# 02_-_POWER.net
KiCad netlist of a schematic drawn in Altium Designer
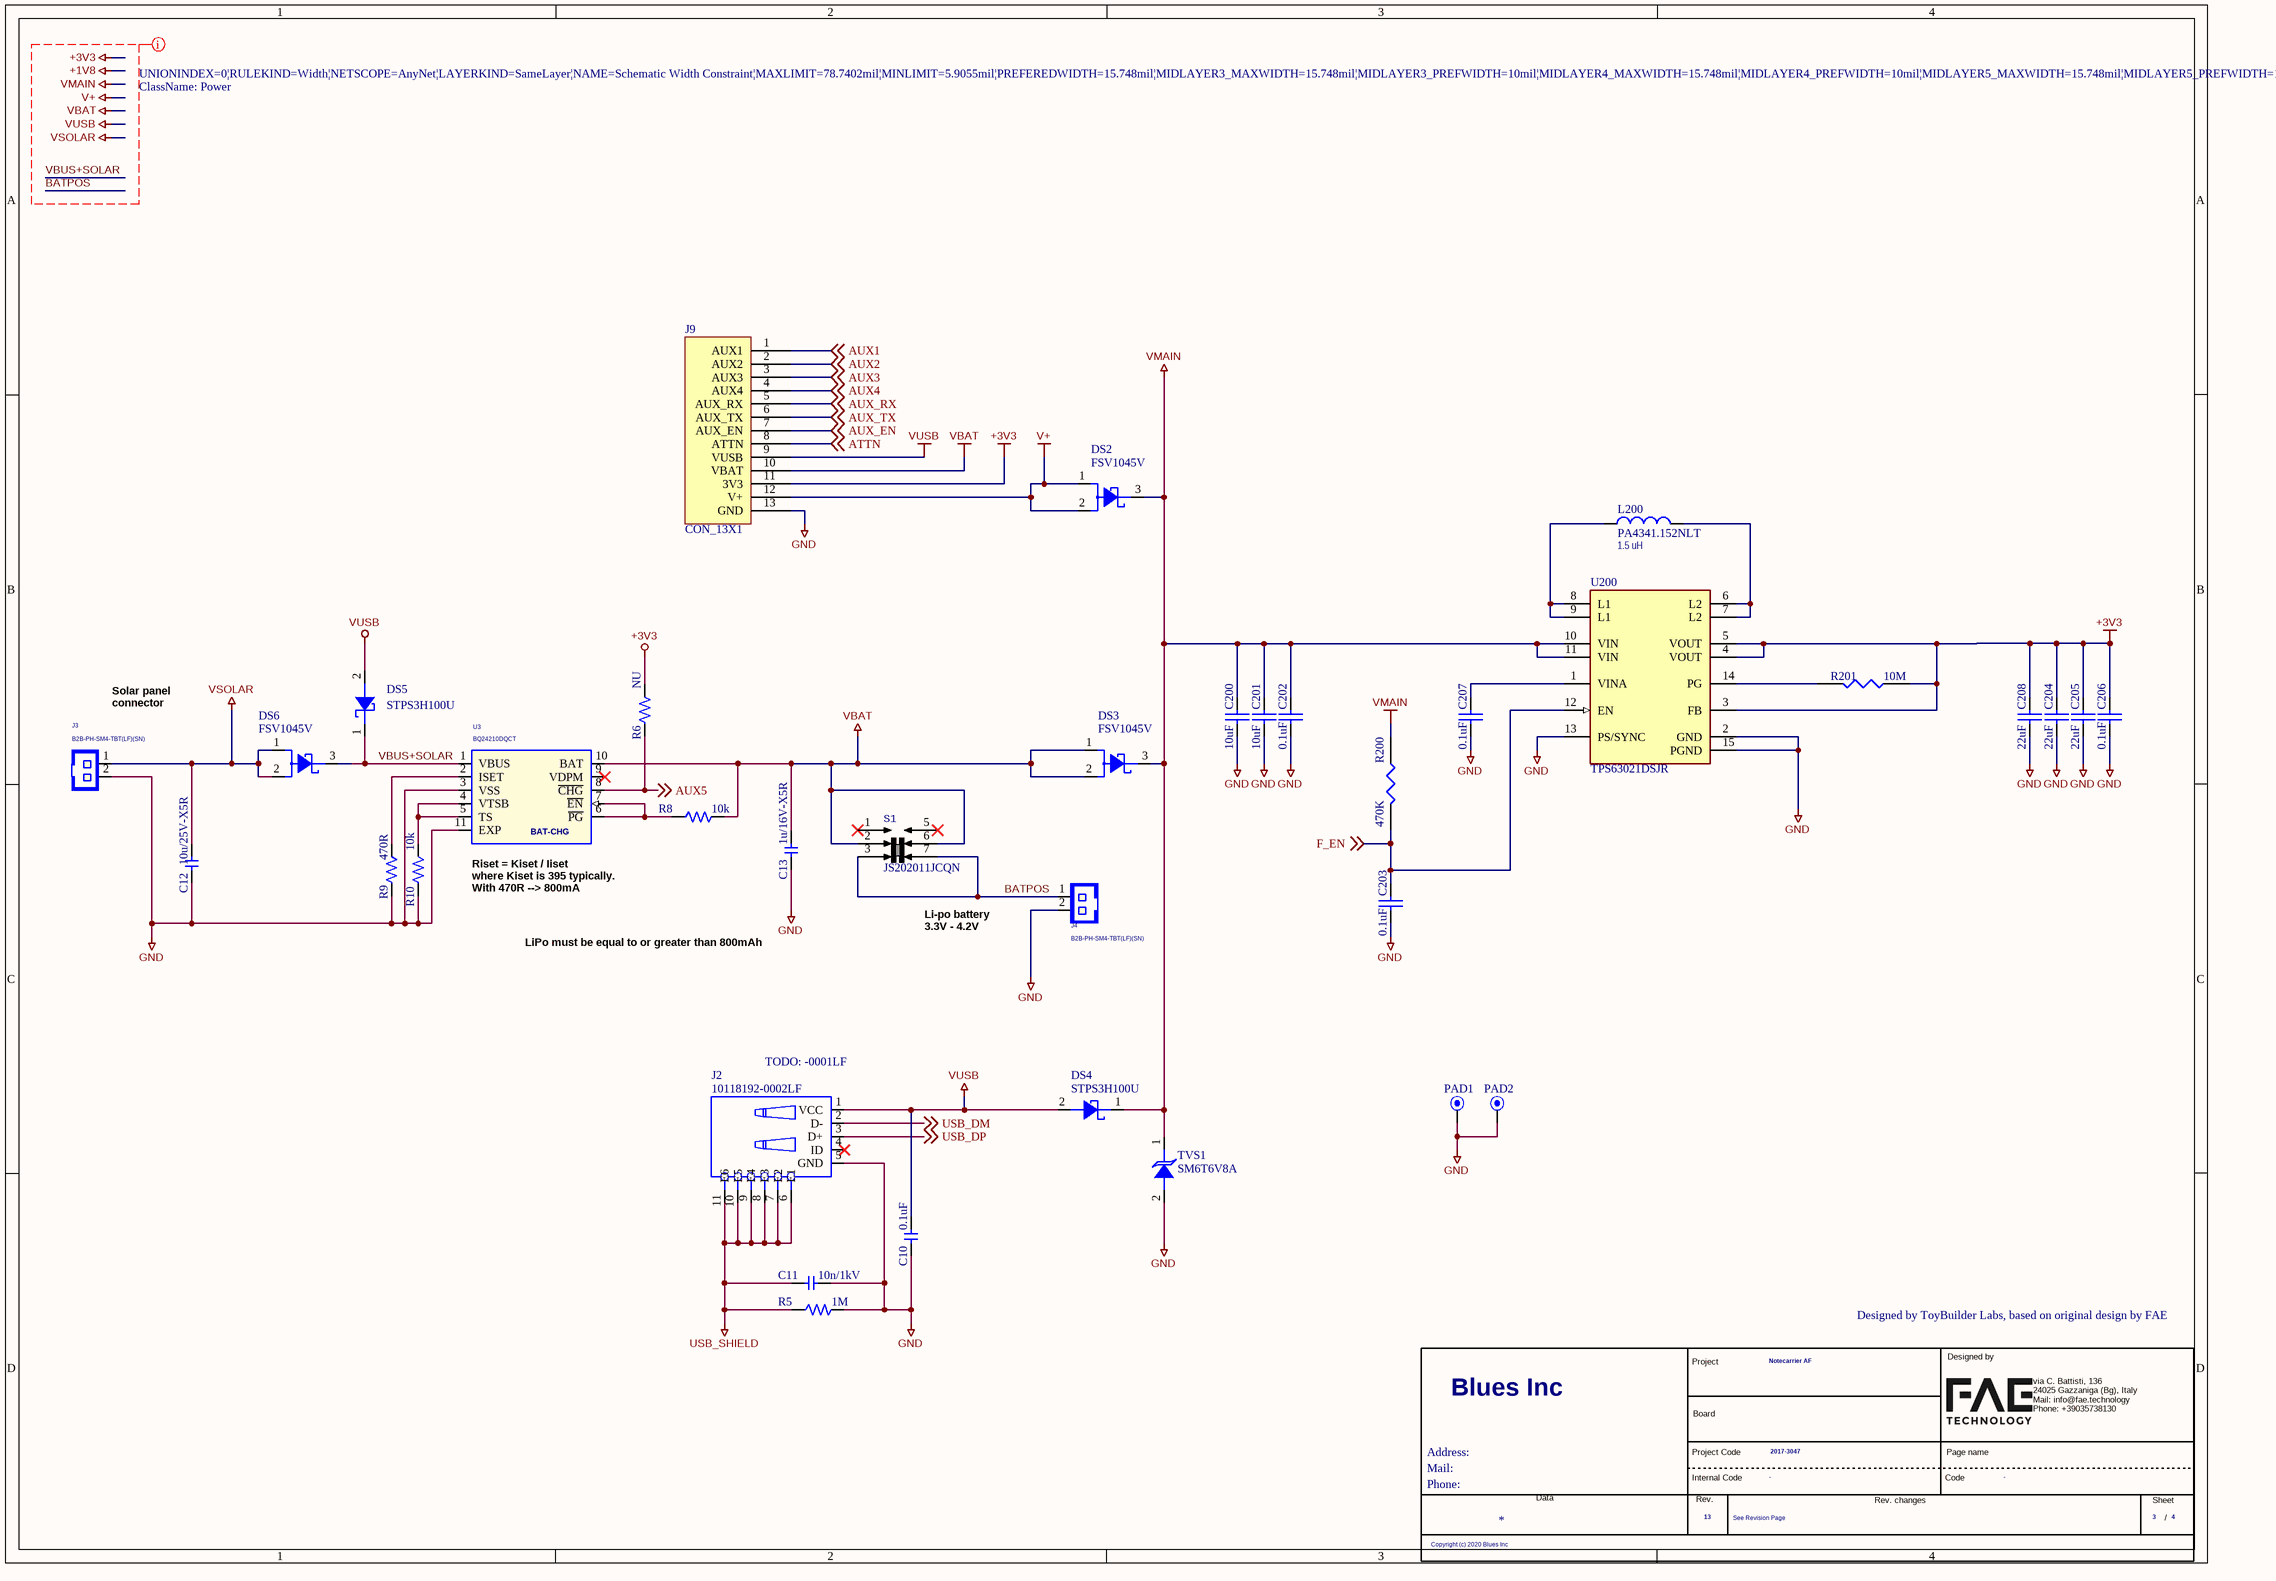
[diagram p0: 02 - POWER.SchDoc]

(export (version "E")
  (design (tool "Eeschema 10.0.6"))
  (components
    (comp (ref "*")
      (value "MyBlues")
      (fields
        (field (name "ADDRESS") "Address:")
        (field (name "COPYRIGHT") "Copyright (c) 2020 Blues Inc")
        (field (name "CUSTOMER CODE") "-")
        (field (name "CUSTOMERNAME") "Blues Inc")
        (field (name "DATABASE") "-")
        (field (name "DOCUMENTOREV") "See Revision Page")
        (field (name "MAIL") "Mail:")
        (field (name "NOME PROGETTO") "Notecarrier AF")
        (field (name "PAGE COUNT") "4")
        (field (name "PAGE NUMBER") "3")
        (field (name "PHONE") "Phone:")
        (field (name "PROJECT CODE") "2017-3047")
        (field (name "REVISION") "13")
      )
      (libsource (lib "*") (part "MyBlues"))
    )
    (comp (ref "C10")
      (value "0.1uF")
      (footprint "CS-C-0402")
      (description "CHIP CAP.CER. 100nF 16V 10% X7R 0402")
      (fields (field (name "MFR") "Yageo"))
      (libsource (lib "*") (part "CS-C-0402-100n/16V"))
    )
    (comp (ref "C11")
      (value "10n/1kV")
      (footprint "CS-C-1206")
      (description "CHIP CAP.CER. 10nF 1000V 10% X7R 1206")
      (libsource (lib "*") (part "CS-C-1206-10n/1kV"))
    )
    (comp (ref "C12")
      (value "10u/25V-X5R")
      (footprint "CS-C-1206")
      (description "CHIP CAP.CER. 10uF 25V X5R 10% 1206")
      (libsource (lib "*") (part "CS-C-1206-10u/25V-X5R"))
    )
    (comp (ref "C13")
      (value "1u/16V-X5R")
      (footprint "CS-C-0402")
      (description "CHIP CAP.CER. 1uF 16V 10% X5R 0402")
      (libsource (lib "*") (part "CS-C-0402-1u/16-X5R"))
    )
    (comp (ref "C200")
      (value "10uF")
      (footprint "0805_C")
      (description "CHIP CAP.CER. 10uF 16V 10% X7R 0805")
      (fields (field (name "MFR") "TDK"))
      (libsource (lib "Cap_SCH") (part "CAP"))
    )
    (comp (ref "C201")
      (value "10uF")
      (footprint "0805_C")
      (description "CHIP CAP.CER. 10uF 16V 10% X7R 0805")
      (fields (field (name "MFR") "TDK"))
      (libsource (lib "Cap_SCH") (part "CAP"))
    )
    (comp (ref "C202")
      (value "0.1uF")
      (footprint "CS-C-0402")
      (description "CHIP CAP.CER. 100nF 16V 10% X7R 0402")
      (fields (field (name "MFR") "Yageo"))
      (libsource (lib "Cap_SCH") (part "CAP"))
    )
    (comp (ref "C203")
      (value "0.1uF")
      (footprint "CS-C-0402")
      (description "CHIP CAP.CER. 100nF 16V 10% X7R 0402")
      (fields (field (name "MFR") "Yageo"))
      (libsource (lib "Cap_SCH") (part "CAP"))
    )
    (comp (ref "C204")
      (value "22uF")
      (footprint "0805_C")
      (description "CHIP CAP.CER. 22uF 16V 10% X7R 0805")
      (fields (field (name "MFR") "TDK"))
      (libsource (lib "Cap_SCH") (part "CAP"))
    )
    (comp (ref "C205")
      (value "22uF")
      (footprint "0805_C")
      (description "CHIP CAP.CER. 22uF 16V 10% X7R 0805")
      (fields (field (name "MFR") "TDK"))
      (libsource (lib "Cap_SCH") (part "CAP"))
    )
    (comp (ref "C206")
      (value "0.1uF")
      (footprint "CS-C-0402")
      (description "CHIP CAP.CER. 100nF 16V 10% X7R 0402")
      (fields (field (name "MFR") "Yageo"))
      (libsource (lib "Cap_SCH") (part "CAP"))
    )
    (comp (ref "C207")
      (value "0.1uF")
      (footprint "CS-C-0402")
      (description "CHIP CAP.CER. 100nF 16V 10% X7R 0402")
      (fields (field (name "MFR") "Yageo"))
      (libsource (lib "Cap_SCH") (part "CAP"))
    )
    (comp (ref "C208")
      (value "22uF")
      (footprint "0805_C")
      (description "CHIP CAP.CER. 22uF 16V 10% X7R 0805")
      (fields (field (name "MFR") "TDK"))
      (libsource (lib "Cap_SCH") (part "CAP"))
    )
    (comp (ref "DS2")
      (value "FSV1045V")
      (footprint "TO277-3")
      (description "DIODO SCHOTTKY 10A 45V FSV1045V TO277-3 SMT")
      (libsource (lib "*") (part "SCHOTTKY - FSV1045V - 10A/45V"))
    )
    (comp (ref "DS3")
      (value "FSV1045V")
      (footprint "TO277-3")
      (description "DIODO SCHOTTKY 10A 45V FSV1045V TO277-3 SMT")
      (libsource (lib "*") (part "SCHOTTKY - FSV1045V - 10A/45V"))
    )
    (comp (ref "DS4")
      (value "STPS3H100U")
      (footprint "SMB")
      (description "DIODO SCHOTTKY 3A 100V STPS3H100U SMB SMT")
      (libsource (lib "*") (part "SCHOTTKY-STPS3H100U - 3A/100V"))
    )
    (comp (ref "DS5")
      (value "STPS3H100U")
      (footprint "SMB")
      (description "DIODO SCHOTTKY 3A 100V STPS3H100U SMB SMT")
      (libsource (lib "*") (part "SCHOTTKY-STPS3H100U - 3A/100V"))
    )
    (comp (ref "DS6")
      (value "FSV1045V")
      (footprint "TO277-3")
      (description "DIODO SCHOTTKY 10A 45V FSV1045V TO277-3 SMT")
      (libsource (lib "*") (part "SCHOTTKY - FSV1045V - 10A/45V"))
    )
    (comp (ref "J2")
      (value "10118192-0002LF")
      (footprint "J-5-0065-FOS-MICROUSB10118192")
      (description "CONN. USB F/90° TIPO MICRO-B C.S. 10118192-0002LF FCI SMT")
      (libsource (lib "*") (part "USB - uUSB-B-10118192-0002LF"))
    )
    (comp (ref "J3")
      (value "B2B-PH-SM4-TBT(LF)(SN)")
      (footprint "J-2-0200-MDS-B2B-PH-SM4")
      (description "CONN. PH 2P M/D P=2 B2B-PH-SM4-TBT(LF)(SN) JST SMT")
      (libsource (lib "") (part "PH - J-2-0200-MDS-B2B-PH-SM4_1"))
    )
    (comp (ref "J4")
      (value "B2B-PH-SM4-TBT(LF)(SN)")
      (footprint "J-2-0200-MDS-B2B-PH-SM4")
      (description "CONN. PH 2P M/D P=2 B2B-PH-SM4-TBT(LF)(SN) JST SMT")
      (libsource (lib "*") (part "PH - J-2-0200-MDS-B2B-PH-SM4"))
    )
    (comp (ref "J9")
      (value "CON_13X1")
      (footprint "WE13S - 2.54")
      (libsource (lib "ATA_BLS_002_NTCR_A0-01_SCHLIB") (part "CON_13X1"))
    )
    (comp (ref "L200")
      (value "PA4341.152NLT")
      (footprint "PULSE PA4341.XXXNLT")
      (description "1.5uH, 9A SMD, (7.6 x 6.9 mm, 3.0 mm highi) 15 mOhm")
      (fields (field (name "MANUFACTURER") "Pulse") (field (name "INDUCTANCE") "1.5 uH"))
      (libsource (lib "TBL Inductors") (part "PA4341.152NLT"))
    )
    (comp (ref "PAD1")
      (value "TPS")
      (footprint "PAD-THT-CAS-0100")
      (description "Mounting Pads")
      (libsource (lib "*") (part "CASTELLATED PAD - 0100"))
    )
    (comp (ref "PAD2")
      (value "TPS")
      (footprint "PAD-THT-CAS-0100")
      (description "Mounting Pads")
      (libsource (lib "*") (part "CASTELLATED PAD - 0100"))
    )
    (comp (ref "R5")
      (value "1M")
      (footprint "RS-1206")
      (description "CHIP RES. 1M 1206 1/4W 1%")
      (libsource (lib "*") (part "RS-1206-1M"))
    )
    (comp (ref "R6")
      (value "NU")
      (footprint "RS-0402")
      (description "CHIP RES. 10K 0402 1/16W 1%")
      (libsource (lib "*") (part "RS-0402-10k"))
    )
    (comp (ref "R8")
      (value "10k")
      (footprint "RS-0402")
      (description "CHIP RES. 10K 0402 1/16W 1%")
      (libsource (lib "*") (part "RS-0402-10k"))
    )
    (comp (ref "R9")
      (value "470R")
      (footprint "RS-0402")
      (description "CHIP RES. 470R 0402 1/16W 1%")
      (libsource (lib "*") (part "RS-0402-470r"))
    )
    (comp (ref "R10")
      (value "10k")
      (footprint "RS-0402")
      (description "CHIP RES. 10K 0402 1/16W 1%")
      (libsource (lib "*") (part "RS-0402-10k"))
    )
    (comp (ref "R200")
      (value "470K")
      (footprint "RS-0402")
      (description "CHIP RES. 470K 0402 1/16W 1%")
      (fields (field (name "MFR") "Vishay / Dale"))
      (libsource (lib "Res_SCH") (part "R1_S"))
    )
    (comp (ref "R201")
      (value "10M")
      (footprint "RS-0402")
      (description "CHIP RES. 10M 0402 1/16W 1%")
      (fields (field (name "MFR") "Vishay / Dale"))
      (libsource (lib "Res_SCH") (part "R1_S"))
    )
    (comp (ref "S1")
      (value "JS202011JCQN")
      (footprint "CK_JS202011JCQN")
      (description "SWITCH SLIDE DPDT 300MA 6V, SMD, J-lead")
      (fields (field (name "MANUFACTURER") "ITT C&K"))
      (libsource (lib "TBL Switches and Buttons") (part "CK_JS202011JCQN"))
    )
    (comp (ref "TVS1")
      (value "SM6T6V8A")
      (footprint "SMB")
      (description "DIODO TVS TRANSIL UNIDIR. 600W 6.8V SM6T6V8A SMB SMT")
      (libsource (lib "*") (part "TVS-UNI - SM6T6V8A - 6.8V/600W"))
    )
    (comp (ref "U3")
      (value "BQ24210DQCT")
      (footprint "WSON10-EXP")
      (description "INTEGRATO BQ24210DQCT TEXAS WSON10 SMT")
      (libsource (lib "*") (part "BAT-CHARGE - BQ24210DQCT"))
    )
    (comp (ref "U200")
      (value "TPS63021DSJR")
      (footprint "FP-DSJ0014A-MFG")
      (description "IC REG BCK BST 3.3V 3.5A 14VSON")
      (fields
        (field (name "MANUFACTURER") "Texas Instruments")
        (field (name "OCTOPART") "https://octopart.com/tps63021dsjr-texas+instruments-17659431")
      )
      (libsource (lib "Altium Content Vault") (part "65dfafb52e5c3d3d60c9dfe8dd4b050"))
    )
  )
  (nets
    (net (code "2") (name "+3V3") (class "Default")
      (node (ref "C204") (pin "1") (pinfunction "1_1") (pintype "passive"))
      (node (ref "C205") (pin "1") (pinfunction "1_1") (pintype "passive"))
      (node (ref "C206") (pin "1") (pinfunction "1_1") (pintype "passive"))
      (node (ref "C208") (pin "1") (pinfunction "1_1") (pintype "passive"))
      (node (ref "J9") (pin "11") (pinfunction "3V3_11") (pintype "passive"))
      (node (ref "R201") (pin "1") (pinfunction "1_1") (pintype "passive"))
      (node (ref "R6") (pin "2") (pinfunction "2_2") (pintype "passive"))
      (node (ref "U200") (pin "3") (pinfunction "FB_3") (pintype "passive"))
      (node (ref "U200") (pin "4") (pinfunction "VOUT_4") (pintype "power_in"))
      (node (ref "U200") (pin "5") (pinfunction "VOUT_5") (pintype "power_in"))
    )
    (net (code "3") (name "/BATPOS") (class "Default")
      (node (ref "J4") (pin "1") (pinfunction "1_1") (pintype "passive"))
      (node (ref "S1") (pin "3") (pinfunction "3_3") (pintype "passive"))
      (node (ref "S1") (pin "7") (pinfunction "7_7") (pintype "passive"))
    )
    (net (code "4") (name "/VBUS+SOLAR") (class "Default")
      (node (ref "DS5") (pin "1") (pinfunction "C_1") (pintype "passive"))
      (node (ref "DS6") (pin "3") (pinfunction "C_3") (pintype "passive"))
      (node (ref "U3") (pin "1") (pinfunction "VBUS_1") (pintype "power_in"))
    )
    (net (code "5") (name "ATTN") (class "Default")
      (node (ref "J9") (pin "8") (pinfunction "ATTN_8") (pintype "passive"))
    )
    (net (code "6") (name "AUX1") (class "Default")
      (node (ref "J9") (pin "1") (pinfunction "AUX1_1") (pintype "passive"))
    )
    (net (code "7") (name "AUX2") (class "Default")
      (node (ref "J9") (pin "2") (pinfunction "AUX2_2") (pintype "passive"))
    )
    (net (code "8") (name "AUX3") (class "Default")
      (node (ref "J9") (pin "3") (pinfunction "AUX3_3") (pintype "passive"))
    )
    (net (code "9") (name "AUX4") (class "Default")
      (node (ref "J9") (pin "4") (pinfunction "AUX4_4") (pintype "passive"))
    )
    (net (code "10") (name "AUX5") (class "Default")
      (node (ref "R6") (pin "1") (pinfunction "1_1") (pintype "passive"))
      (node (ref "U3") (pin "8") (pinfunction "~{CHG}_8") (pintype "open_collector"))
    )
    (net (code "11") (name "AUX_EN") (class "Default")
      (node (ref "J9") (pin "7") (pinfunction "AUX_EN_7") (pintype "passive"))
    )
    (net (code "12") (name "AUX_RX") (class "Default")
      (node (ref "J9") (pin "5") (pinfunction "AUX_RX_5") (pintype "passive"))
    )
    (net (code "13") (name "AUX_TX") (class "Default")
      (node (ref "J9") (pin "6") (pinfunction "AUX_TX_6") (pintype "passive"))
    )
    (net (code "14") (name "F_EN") (class "Default")
      (node (ref "C203") (pin "1") (pinfunction "1_1") (pintype "passive"))
      (node (ref "R200") (pin "2") (pinfunction "2_2") (pintype "passive"))
      (node (ref "U200") (pin "12") (pinfunction "EN_12") (pintype "input"))
    )
    (net (code "15") (name "GND") (class "Default")
      (node (ref "C10") (pin "2") (pinfunction "2_2") (pintype "passive"))
      (node (ref "C11") (pin "2") (pinfunction "2_2") (pintype "passive"))
      (node (ref "C12") (pin "2") (pinfunction "2_2") (pintype "passive"))
      (node (ref "C13") (pin "2") (pinfunction "2_2") (pintype "passive"))
      (node (ref "C200") (pin "2") (pinfunction "2_2") (pintype "passive"))
      (node (ref "C201") (pin "2") (pinfunction "2_2") (pintype "passive"))
      (node (ref "C202") (pin "2") (pinfunction "2_2") (pintype "passive"))
      (node (ref "C203") (pin "2") (pinfunction "2_2") (pintype "passive"))
      (node (ref "C204") (pin "2") (pinfunction "2_2") (pintype "passive"))
      (node (ref "C205") (pin "2") (pinfunction "2_2") (pintype "passive"))
      (node (ref "C206") (pin "2") (pinfunction "2_2") (pintype "passive"))
      (node (ref "C207") (pin "2") (pinfunction "2_2") (pintype "passive"))
      (node (ref "C208") (pin "2") (pinfunction "2_2") (pintype "passive"))
      (node (ref "J2") (pin "5") (pinfunction "GND_5") (pintype "power_in"))
      (node (ref "J3") (pin "2") (pinfunction "2_2") (pintype "passive"))
      (node (ref "J4") (pin "2") (pinfunction "2_2") (pintype "passive"))
      (node (ref "J9") (pin "13") (pinfunction "GND_13") (pintype "passive"))
      (node (ref "PAD1") (pin "1") (pinfunction "1_1") (pintype "passive"))
      (node (ref "PAD2") (pin "1") (pinfunction "1_1") (pintype "passive"))
      (node (ref "R10") (pin "1") (pinfunction "1_1") (pintype "passive"))
      (node (ref "R5") (pin "2") (pinfunction "2_2") (pintype "passive"))
      (node (ref "R9") (pin "1") (pinfunction "1_1") (pintype "passive"))
      (node (ref "TVS1") (pin "2") (pinfunction "A_2") (pintype "passive"))
      (node (ref "U200") (pin "13") (pinfunction "PS/SYNC_13") (pintype "passive"))
      (node (ref "U200") (pin "15") (pinfunction "PGND_15") (pintype "power_in"))
      (node (ref "U200") (pin "2") (pinfunction "GND_2") (pintype "power_in"))
      (node (ref "U3") (pin "11") (pinfunction "EXP_11") (pintype "passive"))
      (node (ref "U3") (pin "3") (pinfunction "VSS_3") (pintype "power_in"))
    )
    (net (code "16") (name "Net-(L200-Pad1)") (class "Default")
      (node (ref "L200") (pin "1") (pinfunction "1_1") (pintype "passive"))
      (node (ref "U200") (pin "8") (pinfunction "L1_8") (pintype "passive"))
      (node (ref "U200") (pin "9") (pinfunction "L1_9") (pintype "passive"))
    )
    (net (code "17") (name "Net-(L200-Pad2)") (class "Default")
      (node (ref "L200") (pin "2") (pinfunction "2_2") (pintype "passive"))
      (node (ref "U200") (pin "6") (pinfunction "L2_6") (pintype "passive"))
      (node (ref "U200") (pin "7") (pinfunction "L2_7") (pintype "passive"))
    )
    (net (code "18") (name "Net-(U3-ISET)") (class "Default")
      (node (ref "R9") (pin "2") (pinfunction "2_2") (pintype "passive"))
      (node (ref "U3") (pin "2") (pinfunction "ISET_2") (pintype "passive"))
    )
    (net (code "19") (name "Net-(U3-TS)") (class "Default")
      (node (ref "R10") (pin "2") (pinfunction "2_2") (pintype "passive"))
      (node (ref "U3") (pin "4") (pinfunction "VTSB_4") (pintype "passive"))
      (node (ref "U3") (pin "5") (pinfunction "TS_5") (pintype "passive"))
    )
    (net (code "20") (name "Net-(U3-~{EN})") (class "Default")
      (node (ref "R8") (pin "1") (pinfunction "1_1") (pintype "passive"))
      (node (ref "U3") (pin "6") (pinfunction "~{PG}_6") (pintype "open_collector"))
      (node (ref "U3") (pin "7") (pinfunction "~{EN}_7") (pintype "input"))
    )
    (net (code "21") (name "Net-(U200-PG)") (class "Default")
      (node (ref "R201") (pin "2") (pinfunction "2_2") (pintype "passive"))
      (node (ref "U200") (pin "14") (pinfunction "PG_14") (pintype "open_collector"))
    )
    (net (code "22") (name "Net-(U200-VINA)") (class "Default")
      (node (ref "C207") (pin "1") (pinfunction "1_1") (pintype "passive"))
      (node (ref "U200") (pin "1") (pinfunction "VINA_1") (pintype "power_in"))
    )
    (net (code "23") (name "USB_DM") (class "Default")
      (node (ref "J2") (pin "2") (pinfunction "D-_2") (pintype "bidirectional"))
    )
    (net (code "24") (name "USB_DP") (class "Default")
      (node (ref "J2") (pin "3") (pinfunction "D+_3") (pintype "bidirectional"))
    )
    (net (code "25") (name "USB_SHIELD") (class "Default")
      (node (ref "C11") (pin "1") (pinfunction "1_1") (pintype "passive"))
      (node (ref "J2") (pin "10") (pinfunction "E5_10") (pintype "passive"))
      (node (ref "J2") (pin "11") (pinfunction "E6_11") (pintype "passive"))
      (node (ref "J2") (pin "6") (pinfunction "E1_6") (pintype "passive"))
      (node (ref "J2") (pin "7") (pinfunction "E2_7") (pintype "passive"))
      (node (ref "J2") (pin "8") (pinfunction "E3_8") (pintype "passive"))
      (node (ref "J2") (pin "9") (pinfunction "E4_9") (pintype "passive"))
      (node (ref "R5") (pin "1") (pinfunction "1_1") (pintype "passive"))
    )
    (net (code "26") (name "V+") (class "Default")
      (node (ref "DS2") (pin "1") (pinfunction "A1_1") (pintype "passive"))
      (node (ref "DS2") (pin "2") (pinfunction "A2_2") (pintype "passive"))
      (node (ref "J9") (pin "12") (pinfunction "V+_12") (pintype "passive"))
    )
    (net (code "27") (name "VBAT") (class "Default")
      (node (ref "C13") (pin "1") (pinfunction "1_1") (pintype "passive"))
      (node (ref "DS3") (pin "1") (pinfunction "A1_1") (pintype "passive"))
      (node (ref "DS3") (pin "2") (pinfunction "A2_2") (pintype "passive"))
      (node (ref "J9") (pin "10") (pinfunction "VBAT_10") (pintype "passive"))
      (node (ref "R8") (pin "2") (pinfunction "2_2") (pintype "passive"))
      (node (ref "S1") (pin "2") (pinfunction "2_2") (pintype "passive"))
      (node (ref "S1") (pin "6") (pinfunction "6_6") (pintype "passive"))
      (node (ref "U3") (pin "10") (pinfunction "BAT_10") (pintype "power_in"))
    )
    (net (code "28") (name "VMAIN") (class "Default")
      (node (ref "C200") (pin "1") (pinfunction "1_1") (pintype "passive"))
      (node (ref "C201") (pin "1") (pinfunction "1_1") (pintype "passive"))
      (node (ref "C202") (pin "1") (pinfunction "1_1") (pintype "passive"))
      (node (ref "DS2") (pin "3") (pinfunction "C_3") (pintype "passive"))
      (node (ref "DS3") (pin "3") (pinfunction "C_3") (pintype "passive"))
      (node (ref "DS4") (pin "1") (pinfunction "C_1") (pintype "passive"))
      (node (ref "R200") (pin "1") (pinfunction "1_1") (pintype "passive"))
      (node (ref "TVS1") (pin "1") (pinfunction "C_1") (pintype "passive"))
      (node (ref "U200") (pin "10") (pinfunction "VIN_10") (pintype "power_in"))
      (node (ref "U200") (pin "11") (pinfunction "VIN_11") (pintype "power_in"))
    )
    (net (code "29") (name "VSOLAR") (class "Default")
      (node (ref "C12") (pin "1") (pinfunction "1_1") (pintype "passive"))
      (node (ref "DS6") (pin "1") (pinfunction "A1_1") (pintype "passive"))
      (node (ref "DS6") (pin "2") (pinfunction "A2_2") (pintype "passive"))
      (node (ref "J3") (pin "1") (pinfunction "1_1") (pintype "passive"))
    )
    (net (code "30") (name "VUSB") (class "Default")
      (node (ref "C10") (pin "1") (pinfunction "1_1") (pintype "passive"))
      (node (ref "DS4") (pin "2") (pinfunction "A_2") (pintype "passive"))
      (node (ref "DS5") (pin "2") (pinfunction "A_2") (pintype "passive"))
      (node (ref "J2") (pin "1") (pinfunction "VCC_1") (pintype "power_in"))
      (node (ref "J9") (pin "9") (pinfunction "VUSB_9") (pintype "passive"))
    )
    (net (code "31") (name "unconnected-(J2-ID-Pad4)") (class "Default")
      (node (ref "J2") (pin "4") (pinfunction "ID_4") (pintype "passive+no_connect"))
    )
    (net (code "32") (name "unconnected-(S1-Pad1)") (class "Default")
      (node (ref "S1") (pin "1") (pinfunction "1_1") (pintype "passive+no_connect"))
    )
    (net (code "33") (name "unconnected-(S1-Pad5)") (class "Default")
      (node (ref "S1") (pin "5") (pinfunction "5_5") (pintype "passive+no_connect"))
    )
    (net (code "34") (name "unconnected-(U3-VDPM-Pad9)") (class "Default")
      (node (ref "U3") (pin "9") (pinfunction "VDPM_9") (pintype "passive+no_connect"))
    )
  )
)
